# hackfest.net
KiCad netlist of a schematic drawn in EAGLE
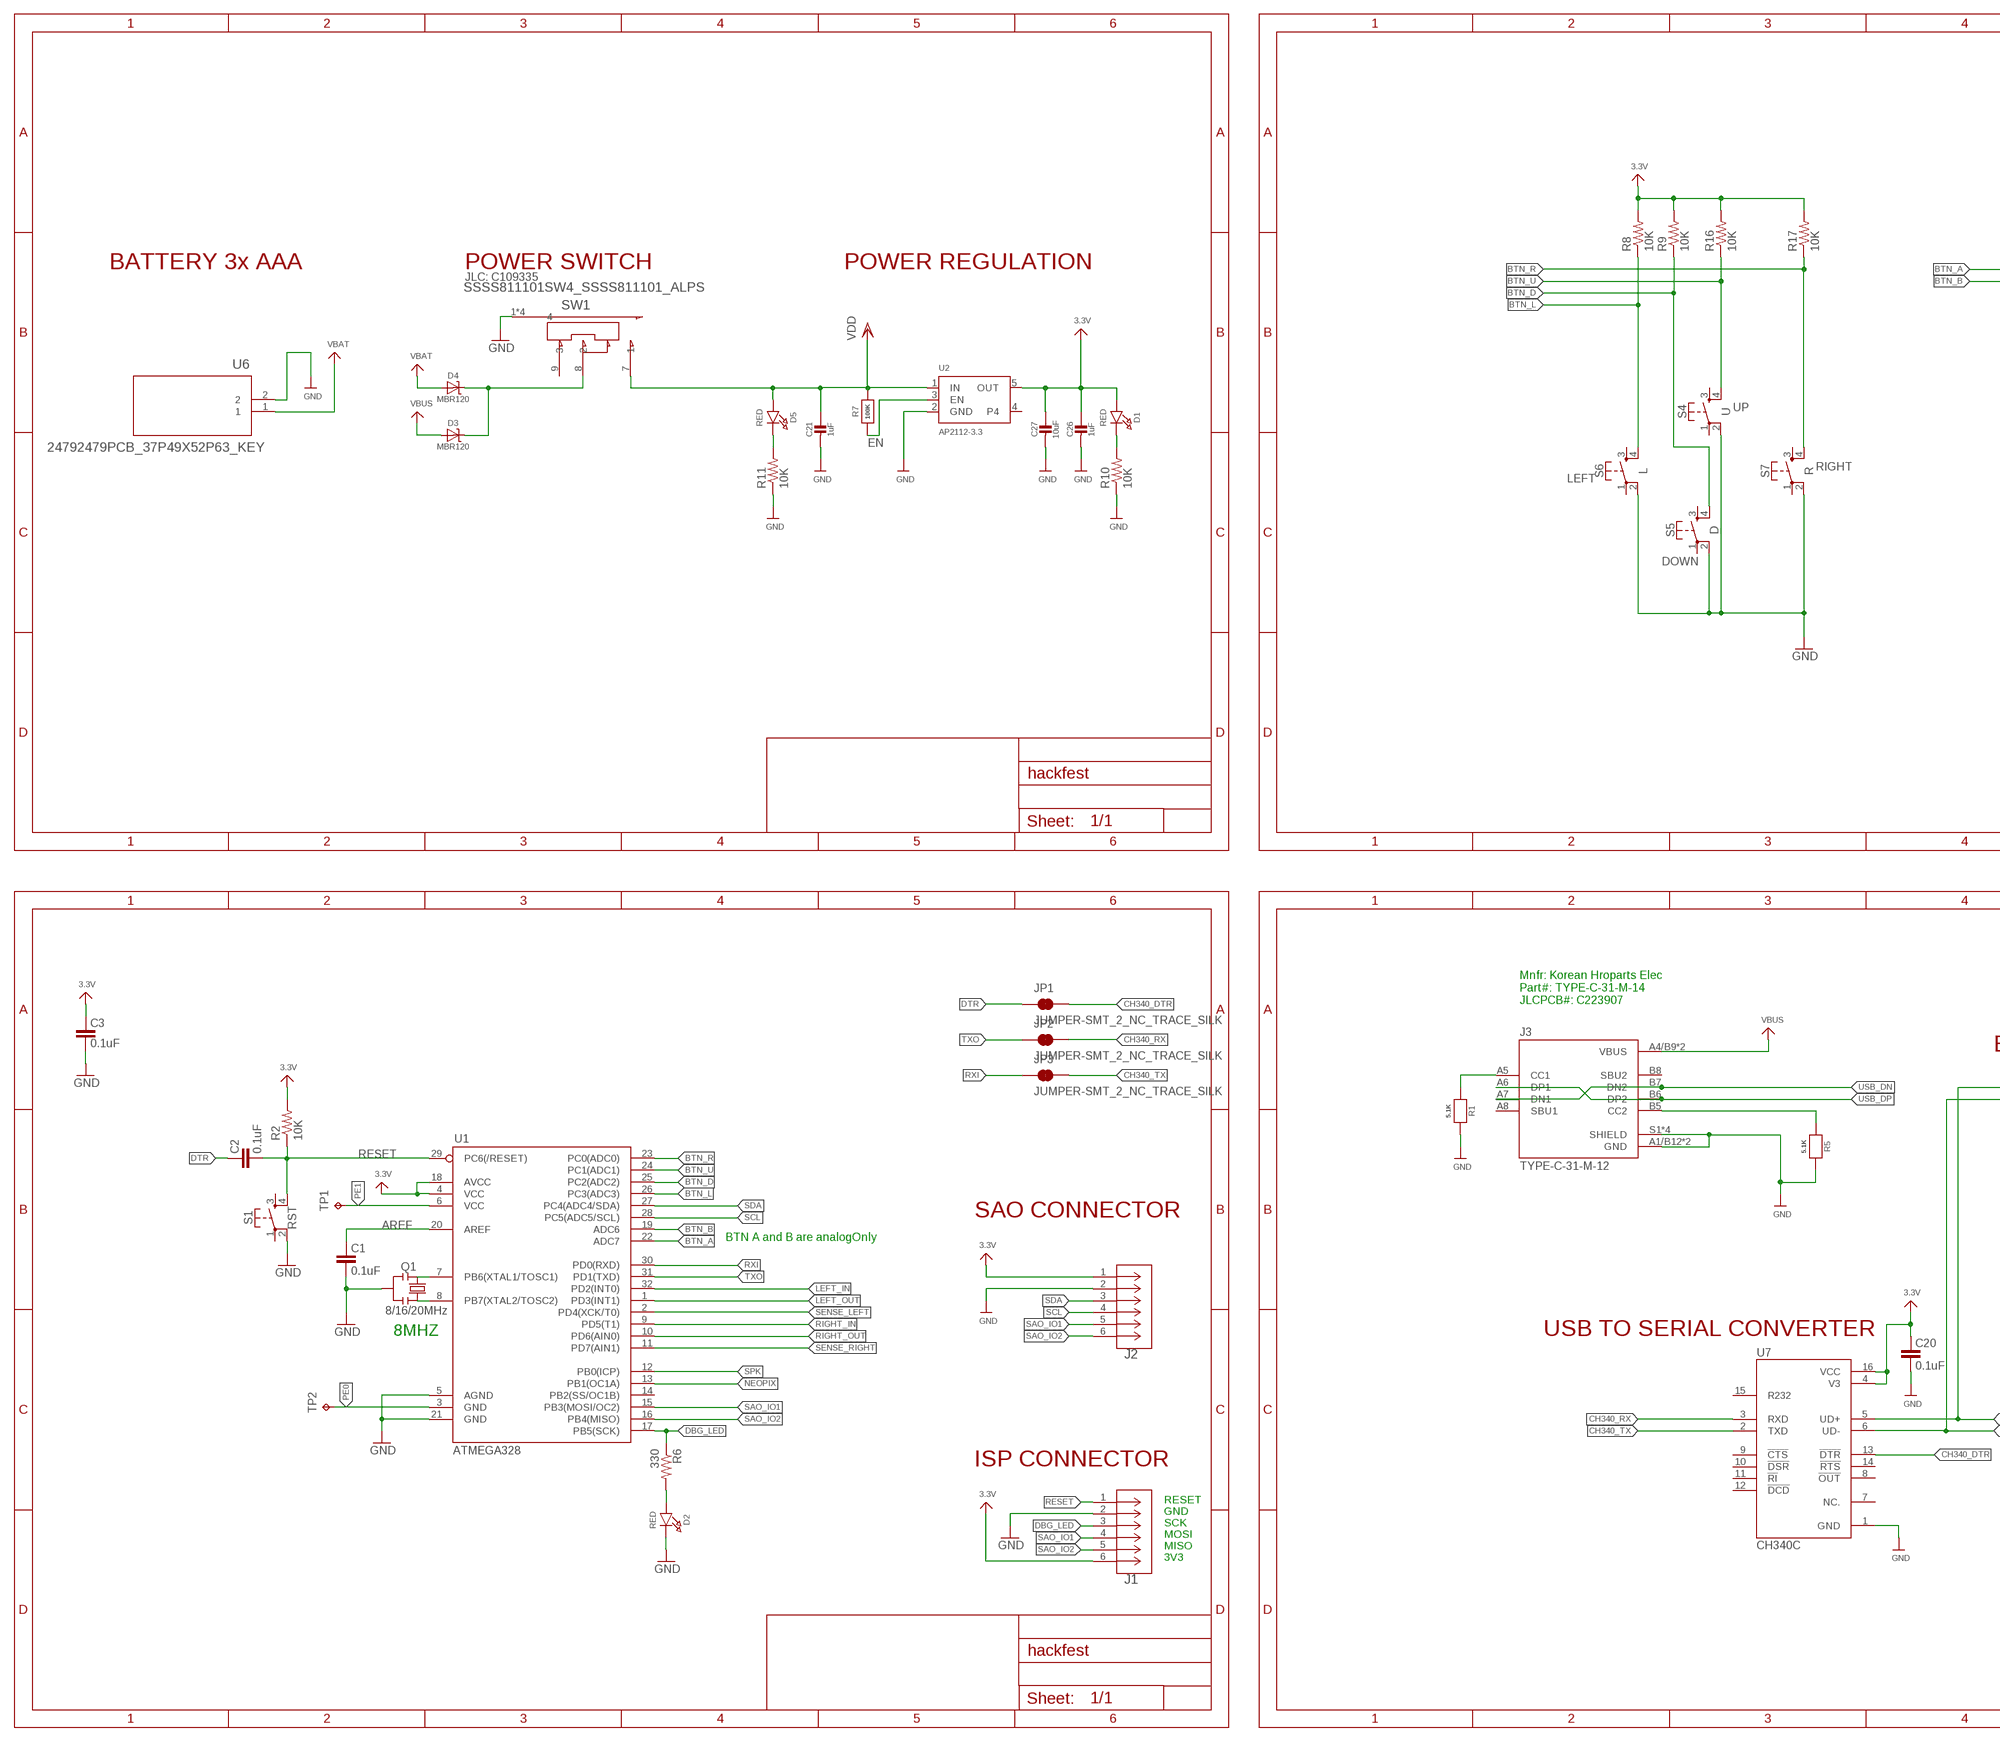
[diagram p0: schematic, sheet 1, part 1 of 2]
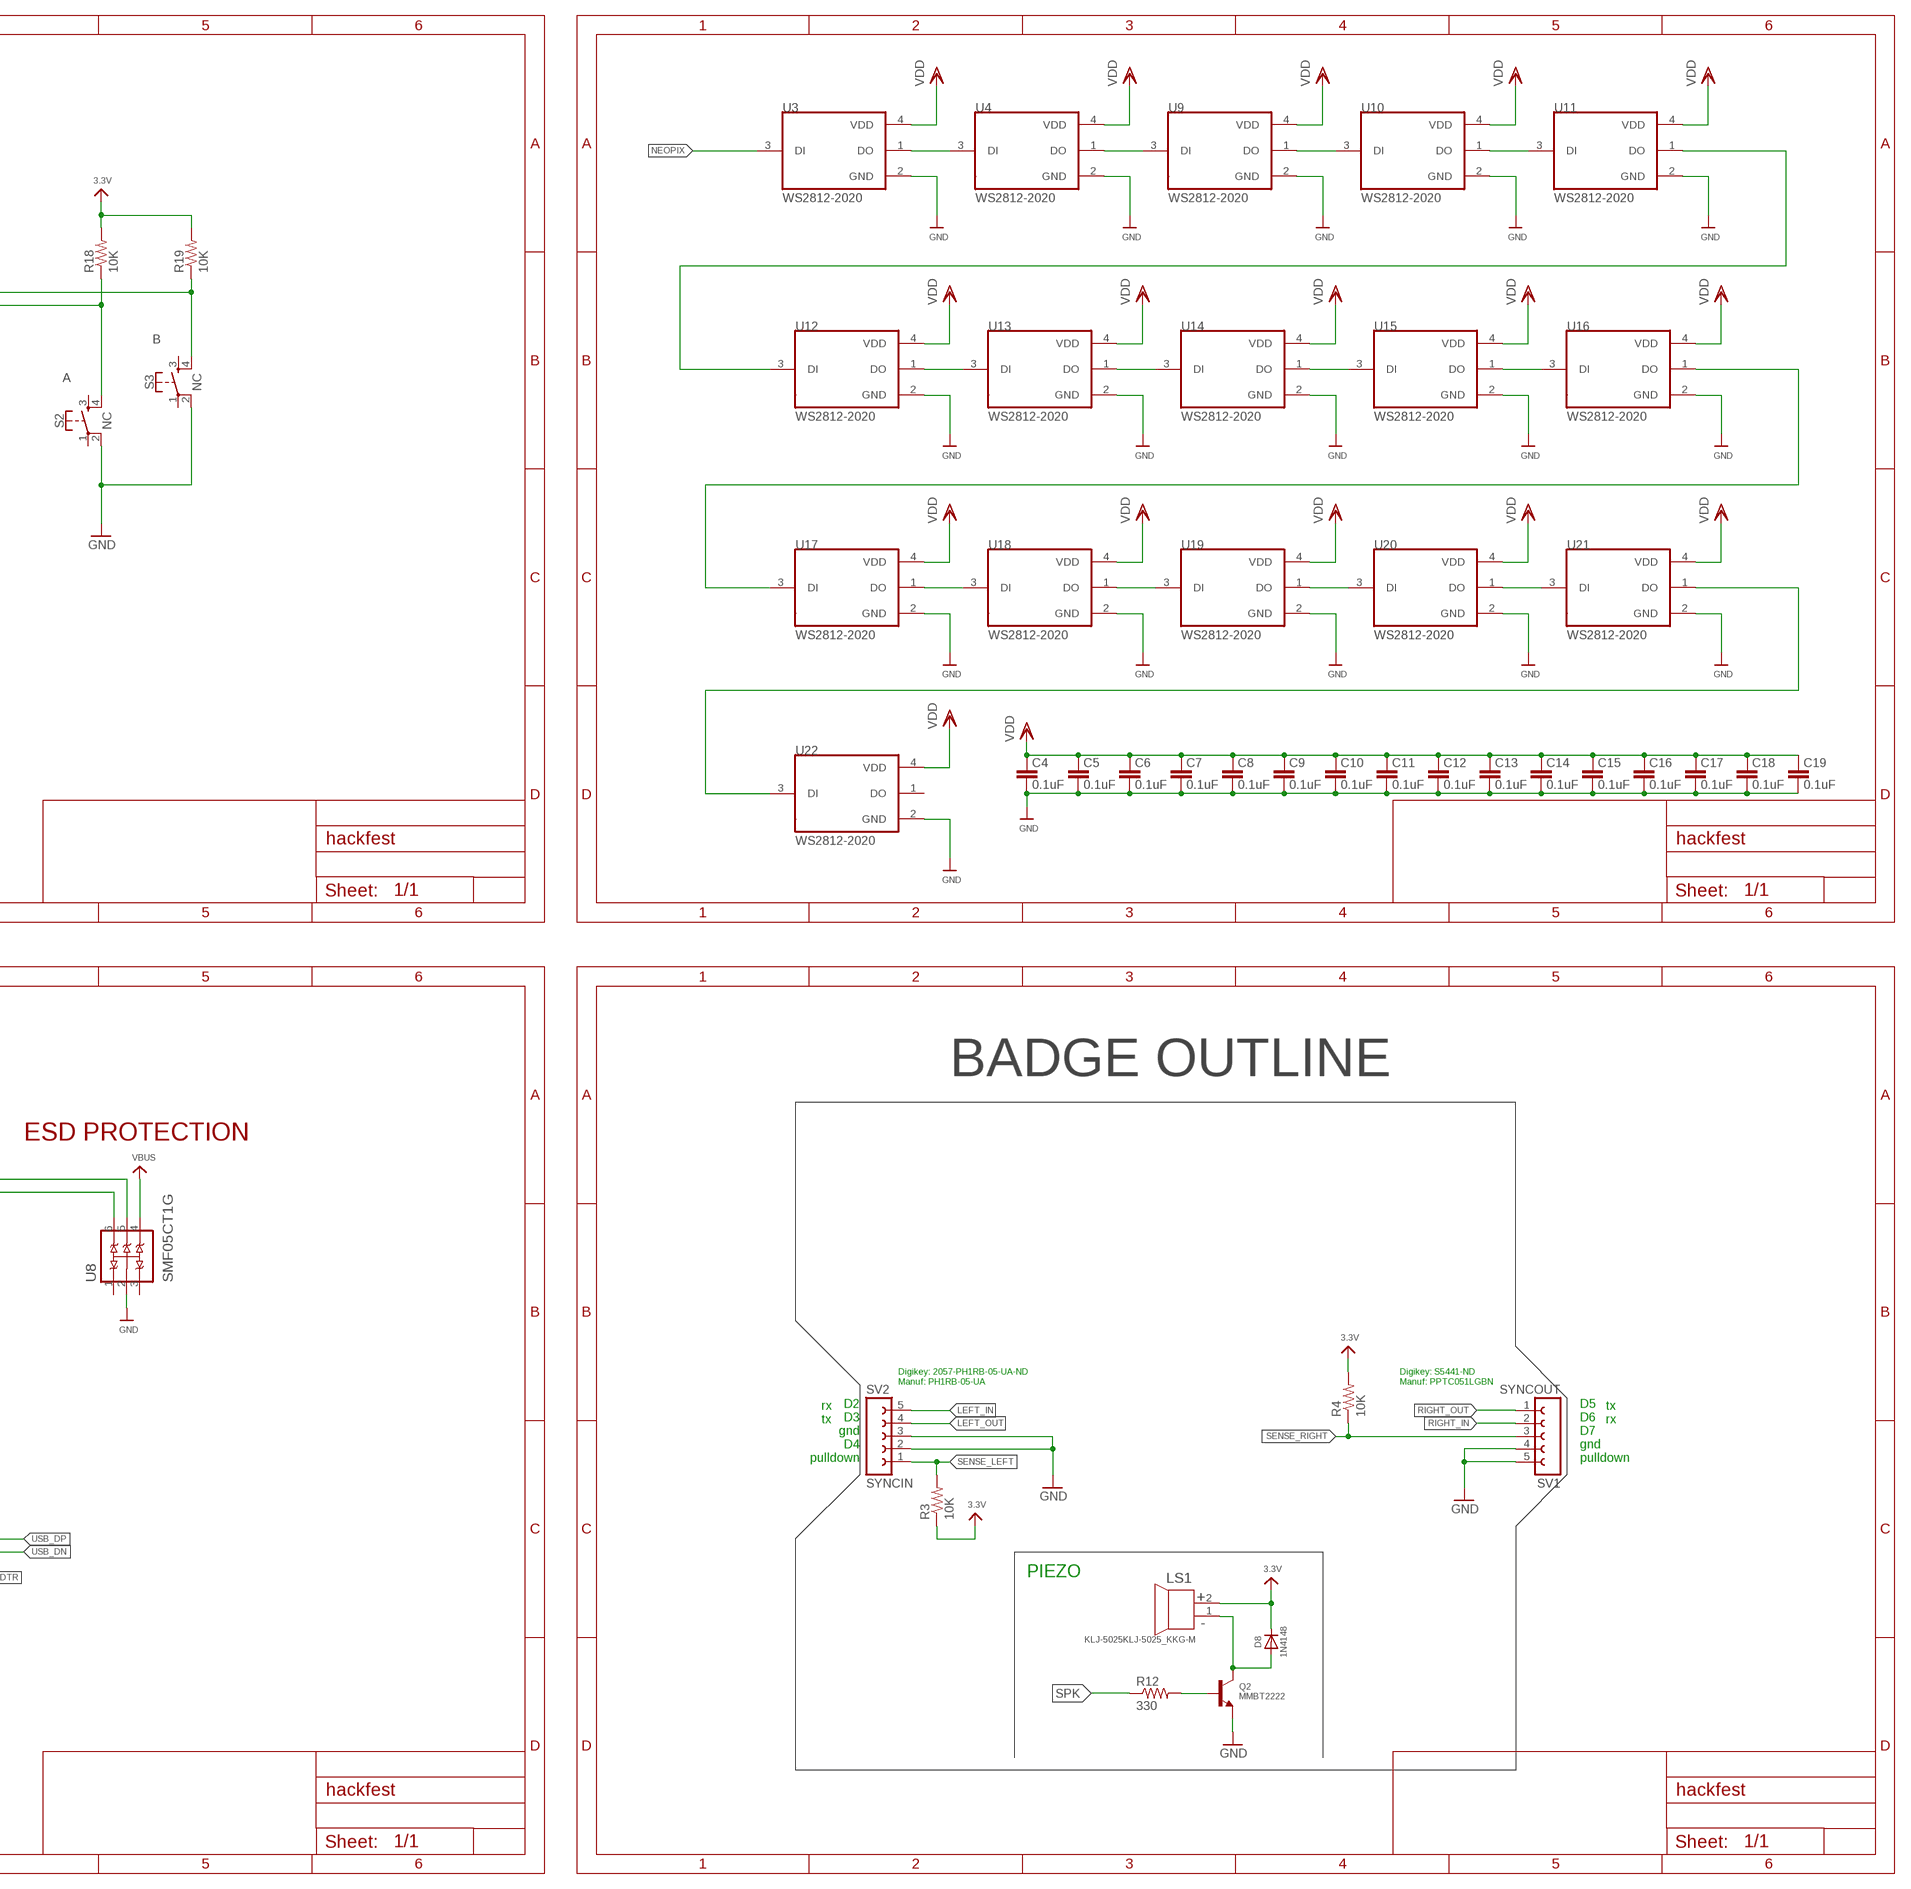
[diagram p1: schematic, sheet 1, part 2 of 2]

(export (version "E")
  (design (tool "Eeschema 10.0.6"))
  (components
    (comp (ref "C1")
      (value "0.1uF")
      (footprint "eagle-import:0603-CAP")
      (libsource (lib "eagle-import") (part "CAP0603-CAP"))
    )
    (comp (ref "C2")
      (value "0.1uF")
      (footprint "eagle-import:0603-CAP")
      (libsource (lib "eagle-import") (part "CAP0603-CAP"))
    )
    (comp (ref "C3")
      (value "0.1uF")
      (footprint "eagle-import:0603-CAP")
      (libsource (lib "eagle-import") (part "CAP0603-CAP"))
    )
    (comp (ref "C4")
      (value "0.1uF")
      (footprint "eagle-import:0603-CAP")
      (libsource (lib "eagle-import") (part "CAP0603-CAP"))
    )
    (comp (ref "C5")
      (value "0.1uF")
      (footprint "eagle-import:0603-CAP")
      (libsource (lib "eagle-import") (part "CAP0603-CAP"))
    )
    (comp (ref "C6")
      (value "0.1uF")
      (footprint "eagle-import:0603-CAP")
      (libsource (lib "eagle-import") (part "CAP0603-CAP"))
    )
    (comp (ref "C7")
      (value "0.1uF")
      (footprint "eagle-import:0603-CAP")
      (libsource (lib "eagle-import") (part "CAP0603-CAP"))
    )
    (comp (ref "C8")
      (value "0.1uF")
      (footprint "eagle-import:0603-CAP")
      (libsource (lib "eagle-import") (part "CAP0603-CAP"))
    )
    (comp (ref "C9")
      (value "0.1uF")
      (footprint "eagle-import:0603-CAP")
      (libsource (lib "eagle-import") (part "CAP0603-CAP"))
    )
    (comp (ref "C10")
      (value "0.1uF")
      (footprint "eagle-import:0603-CAP")
      (libsource (lib "eagle-import") (part "CAP0603-CAP"))
    )
    (comp (ref "C11")
      (value "0.1uF")
      (footprint "eagle-import:0603-CAP")
      (libsource (lib "eagle-import") (part "CAP0603-CAP"))
    )
    (comp (ref "C12")
      (value "0.1uF")
      (footprint "eagle-import:0603-CAP")
      (libsource (lib "eagle-import") (part "CAP0603-CAP"))
    )
    (comp (ref "C13")
      (value "0.1uF")
      (footprint "eagle-import:0603-CAP")
      (libsource (lib "eagle-import") (part "CAP0603-CAP"))
    )
    (comp (ref "C14")
      (value "0.1uF")
      (footprint "eagle-import:0603-CAP")
      (libsource (lib "eagle-import") (part "CAP0603-CAP"))
    )
    (comp (ref "C15")
      (value "0.1uF")
      (footprint "eagle-import:0603-CAP")
      (libsource (lib "eagle-import") (part "CAP0603-CAP"))
    )
    (comp (ref "C16")
      (value "0.1uF")
      (footprint "eagle-import:0603-CAP")
      (libsource (lib "eagle-import") (part "CAP0603-CAP"))
    )
    (comp (ref "C17")
      (value "0.1uF")
      (footprint "eagle-import:0603-CAP")
      (libsource (lib "eagle-import") (part "CAP0603-CAP"))
    )
    (comp (ref "C18")
      (value "0.1uF")
      (footprint "eagle-import:0603-CAP")
      (libsource (lib "eagle-import") (part "CAP0603-CAP"))
    )
    (comp (ref "C19")
      (value "0.1uF")
      (footprint "eagle-import:0603-CAP")
      (libsource (lib "eagle-import") (part "CAP0603-CAP"))
    )
    (comp (ref "C20")
      (value "0.1uF")
      (footprint "eagle-import:0603-CAP")
      (libsource (lib "eagle-import") (part "CAP0603-CAP"))
    )
    (comp (ref "C21")
      (value "1uF")
      (footprint "eagle-import:0603-NO@1")
      (libsource (lib "eagle-import") (part "CAP_CERAMIC0603_NO"))
    )
    (comp (ref "C26")
      (value "1uF")
      (footprint "eagle-import:0603-NO@1")
      (libsource (lib "eagle-import") (part "CAP_CERAMIC0603_NO"))
    )
    (comp (ref "C27")
      (value "10uF")
      (footprint "eagle-import:0805-NO")
      (libsource (lib "eagle-import") (part "CAP_CERAMIC0805-NOOUTLINE"))
    )
    (comp (ref "D1")
      (value "RED")
      (footprint "eagle-import:CHIPLED_0805_NOOUTLINE")
      (libsource (lib "eagle-import") (part "LED0805_NOOUTLINE"))
    )
    (comp (ref "D2")
      (value "RED")
      (footprint "eagle-import:CHIPLED_0805_NOOUTLINE")
      (libsource (lib "eagle-import") (part "LED0805_NOOUTLINE"))
    )
    (comp (ref "D3")
      (value "MBR120")
      (footprint "eagle-import:SOD-123")
      (libsource (lib "eagle-import") (part "DIODE-SCHOTTKYSOD-123"))
    )
    (comp (ref "D4")
      (value "MBR120")
      (footprint "eagle-import:SOD-123")
      (libsource (lib "eagle-import") (part "DIODE-SCHOTTKYSOD-123"))
    )
    (comp (ref "D5")
      (value "RED")
      (footprint "eagle-import:CHIPLED_0805_NOOUTLINE")
      (libsource (lib "eagle-import") (part "LED0805_NOOUTLINE"))
    )
    (comp (ref "D8")
      (value "1N4148")
      (footprint "eagle-import:SOD-323")
      (libsource (lib "eagle-import") (part "DIODESOD-323"))
    )
    (comp (ref "J1")
      (value "SSW-103-22-F-D-VS-K-TRCON3_SSW-D-DUMZ_HDR_SAI")
      (footprint "eagle-import:CON3_SSW-D-DUMZ_HDR_SAI")
      (fields
        (field (name "MANUFACTURER_PART_NUMBER") "SSW-103-22-F-D-VS-K-TR")
        (field (name "COPYRIGHT") "Copyright (C) 2022 Ultra Librarian. All rights reserved.")
      )
      (libsource (lib "eagle-import") (part "SSW-103-22-F-D-VS-K-TRCON3_SSW-D-DUMZ_HDR_SAI"))
    )
    (comp (ref "J2")
      (value "SSW-103-22-F-D-VS-K-TRCON3_SSW-D-DUMZ_HDR_SAI")
      (footprint "eagle-import:CON3_SSW-D-DUMZ_HDR_SAI")
      (fields
        (field (name "MANUFACTURER_PART_NUMBER") "SSW-103-22-F-D-VS-K-TR")
        (field (name "COPYRIGHT") "Copyright (C) 2022 Ultra Librarian. All rights reserved.")
      )
      (libsource (lib "eagle-import") (part "SSW-103-22-F-D-VS-K-TRCON3_SSW-D-DUMZ_HDR_SAI"))
    )
    (comp (ref "J3")
      (value "TYPE-C-31-M-12")
      (footprint "eagle-import:HRO_TYPE-C-31-M-12")
      (fields (field (name "MANUFACTURER") "HRO Electronics Co., Ltd."))
      (libsource (lib "eagle-import") (part "TYPE-C-31-M-12"))
    )
    (comp (ref "JP1")
      (value "JUMPER-SMT_2_NC_TRACE_SILK")
      (footprint "eagle-import:SMT-JUMPER_2_NC_TRACE_SILK")
      (libsource (lib "eagle-import") (part "JUMPER-SMT_2_NC_TRACE_SILK"))
    )
    (comp (ref "JP2")
      (value "JUMPER-SMT_2_NC_TRACE_SILK")
      (footprint "eagle-import:SMT-JUMPER_2_NC_TRACE_SILK")
      (libsource (lib "eagle-import") (part "JUMPER-SMT_2_NC_TRACE_SILK"))
    )
    (comp (ref "JP3")
      (value "JUMPER-SMT_2_NC_TRACE_SILK")
      (footprint "eagle-import:SMT-JUMPER_2_NC_TRACE_SILK")
      (libsource (lib "eagle-import") (part "JUMPER-SMT_2_NC_TRACE_SILK"))
    )
    (comp (ref "LS1")
      (value "KLJ-5025KLJ-5025_KKG-M")
      (footprint "eagle-import:KLJ-5025_KKG-M")
      (fields
        (field (name "MANUFACTURER_PART_NUMBER") "KLJ-5025")
        (field (name "COPYRIGHT") "Copyright (C) 2024 Ultra Librarian. All rights reserved.")
      )
      (libsource (lib "eagle-import") (part "KLJ-5025KLJ-5025_KKG-M"))
    )
    (comp (ref "Q1")
      (value "8/16/20MHz")
      (footprint "eagle-import:RESONATOR-SMD-1_1")
      (libsource (lib "eagle-import") (part "RESONATOR1{colon}1"))
    )
    (comp (ref "Q2")
      (value "MMBT2222")
      (footprint "eagle-import:SOT23-WIDE")
      (libsource (lib "eagle-import") (part "TRANSISTOR_NPNWIDE"))
    )
    (comp (ref "R1")
      (value "5.1K")
      (footprint "eagle-import:0603-NO")
      (libsource (lib "eagle-import") (part "RESISTOR_0603_NOOUT"))
    )
    (comp (ref "R2")
      (value "10K")
      (footprint "eagle-import:0603-RES")
      (libsource (lib "eagle-import") (part "RESISTOR0603-RES"))
    )
    (comp (ref "R3")
      (value "10K")
      (footprint "eagle-import:0603-RES")
      (libsource (lib "eagle-import") (part "RESISTOR0603-RES"))
    )
    (comp (ref "R4")
      (value "10K")
      (footprint "eagle-import:0603-RES")
      (libsource (lib "eagle-import") (part "RESISTOR0603-RES"))
    )
    (comp (ref "R5")
      (value "5.1K")
      (footprint "eagle-import:0603-NO")
      (libsource (lib "eagle-import") (part "RESISTOR_0603_NOOUT"))
    )
    (comp (ref "R6")
      (value "330")
      (footprint "eagle-import:0603-RES")
      (libsource (lib "eagle-import") (part "RESISTOR0603-RES"))
    )
    (comp (ref "R7")
      (value "100K")
      (footprint "eagle-import:0603-NO")
      (libsource (lib "eagle-import") (part "RESISTOR_0603_NOOUT"))
    )
    (comp (ref "R8")
      (value "10K")
      (footprint "eagle-import:0603-RES")
      (libsource (lib "eagle-import") (part "RESISTOR0603-RES"))
    )
    (comp (ref "R9")
      (value "10K")
      (footprint "eagle-import:0603-RES")
      (libsource (lib "eagle-import") (part "RESISTOR0603-RES"))
    )
    (comp (ref "R10")
      (value "10K")
      (footprint "eagle-import:0603-RES")
      (libsource (lib "eagle-import") (part "RESISTOR0603-RES"))
    )
    (comp (ref "R11")
      (value "10K")
      (footprint "eagle-import:0603-RES")
      (libsource (lib "eagle-import") (part "RESISTOR0603-RES"))
    )
    (comp (ref "R12")
      (value "330")
      (footprint "eagle-import:0603-RES")
      (libsource (lib "eagle-import") (part "RESISTOR0603-RES"))
    )
    (comp (ref "R16")
      (value "10K")
      (footprint "eagle-import:0603-RES")
      (libsource (lib "eagle-import") (part "RESISTOR0603-RES"))
    )
    (comp (ref "R17")
      (value "10K")
      (footprint "eagle-import:0603-RES")
      (libsource (lib "eagle-import") (part "RESISTOR0603-RES"))
    )
    (comp (ref "R18")
      (value "10K")
      (footprint "eagle-import:0603-RES")
      (libsource (lib "eagle-import") (part "RESISTOR0603-RES"))
    )
    (comp (ref "R19")
      (value "10K")
      (footprint "eagle-import:0603-RES")
      (libsource (lib "eagle-import") (part "RESISTOR0603-RES"))
    )
    (comp (ref "S1")
      (value "RST")
      (footprint "eagle-import:TACTILE_SWITCH_SMD_5.2MM")
      (libsource (lib "eagle-import") (part "MOMENTARY-SWITCH-SPST-2-SMD-5.2MM"))
    )
    (comp (ref "S2")
      (value "NC")
      (footprint "eagle-import:TACTILE_SWITCH_SMD_5.2MM")
      (libsource (lib "eagle-import") (part "MOMENTARY-SWITCH-SPST-2-SMD-5.2MM"))
    )
    (comp (ref "S3")
      (value "NC")
      (footprint "eagle-import:TACTILE_SWITCH_SMD_5.2MM")
      (libsource (lib "eagle-import") (part "MOMENTARY-SWITCH-SPST-2-SMD-5.2MM"))
    )
    (comp (ref "S4")
      (value "U")
      (footprint "eagle-import:TACTILE_SWITCH_SMD_5.2MM")
      (libsource (lib "eagle-import") (part "MOMENTARY-SWITCH-SPST-2-SMD-5.2MM"))
    )
    (comp (ref "S5")
      (value "D")
      (footprint "eagle-import:TACTILE_SWITCH_SMD_5.2MM")
      (libsource (lib "eagle-import") (part "MOMENTARY-SWITCH-SPST-2-SMD-5.2MM"))
    )
    (comp (ref "S6")
      (value "L")
      (footprint "eagle-import:TACTILE_SWITCH_SMD_5.2MM")
      (libsource (lib "eagle-import") (part "MOMENTARY-SWITCH-SPST-2-SMD-5.2MM"))
    )
    (comp (ref "S7")
      (value "R")
      (footprint "eagle-import:TACTILE_SWITCH_SMD_5.2MM")
      (libsource (lib "eagle-import") (part "MOMENTARY-SWITCH-SPST-2-SMD-5.2MM"))
    )
    (comp (ref "SV1")
      (value "SYNCOUT")
      (footprint "eagle-import:FE05W")
      (libsource (lib "eagle-import") (part "FE05W"))
    )
    (comp (ref "SV2")
      (value "SYNCIN")
      (footprint "eagle-import:FE05W")
      (libsource (lib "eagle-import") (part "FE05W"))
    )
    (comp (ref "SW1")
      (value "SSSS811101SW4_SSSS811101_ALPS")
      (footprint "eagle-import:SW4_SSSS811101_ALPS")
      (fields
        (field (name "MANUFACTURER_PART_NUMBER") "SSSS811101")
        (field (name "COPYRIGHT") "Copyright (C) 2023 Ultra Librarian. All rights reserved.")
      )
      (libsource (lib "eagle-import") (part "SSSS811101SW4_SSSS811101_ALPS"))
    )
    (comp (ref "TP1")
      (value "TPB1,27")
      (footprint "eagle-import:B1,27")
      (libsource (lib "eagle-import") (part "TPB1,27"))
    )
    (comp (ref "TP2")
      (value "TPB1,27")
      (footprint "eagle-import:B1,27")
      (libsource (lib "eagle-import") (part "TPB1,27"))
    )
    (comp (ref "U1")
      (value "ATMEGA328")
      (footprint "eagle-import:TQFP32-08")
      (libsource (lib "eagle-import") (part "ATMEGA168"))
    )
    (comp (ref "U2")
      (value "AP2112-3.3")
      (footprint "eagle-import:SOT23-5")
      (libsource (lib "eagle-import") (part "VREG_SOT23-5"))
    )
    (comp (ref "U3")
      (value "WS2812-2020")
      (footprint "eagle-import:LED_WS2812-2020")
      (fields (field (name "MF") "Worldsemi"))
      (libsource (lib "eagle-import") (part "WS2812-2020"))
    )
    (comp (ref "U4")
      (value "WS2812-2020")
      (footprint "eagle-import:LED_WS2812-2020")
      (fields (field (name "MF") "Worldsemi"))
      (libsource (lib "eagle-import") (part "WS2812-2020"))
    )
    (comp (ref "U6")
      (value "24792479PCB_37P49X52P63_KEY")
      (footprint "eagle-import:2479PCB_37P49X52P63_KEY")
      (fields
        (field (name "MANUFACTURER_PART_NUMBER") "2479")
        (field (name "COPYRIGHT") "Copyright (C) 2022 Ultra Librarian. All rights reserved.")
      )
      (libsource (lib "eagle-import") (part "24792479PCB_37P49X52P63_KEY"))
    )
    (comp (ref "U7")
      (value "CH340C")
      (footprint "eagle-import:SOIC127P600X180-16N")
      (fields (field (name "MF") "WCH"))
      (libsource (lib "eagle-import") (part "CH340C"))
    )
    (comp (ref "U8")
      (value "SMF05CT1G")
      (footprint "eagle-import:SOT65P210X110-6N")
      (fields (field (name "MF") "ON Semiconductor"))
      (libsource (lib "eagle-import") (part "SMF05CT1G"))
    )
    (comp (ref "U9")
      (value "WS2812-2020")
      (footprint "eagle-import:LED_WS2812-2020")
      (fields (field (name "MF") "Worldsemi"))
      (libsource (lib "eagle-import") (part "WS2812-2020"))
    )
    (comp (ref "U10")
      (value "WS2812-2020")
      (footprint "eagle-import:LED_WS2812-2020")
      (fields (field (name "MF") "Worldsemi"))
      (libsource (lib "eagle-import") (part "WS2812-2020"))
    )
    (comp (ref "U11")
      (value "WS2812-2020")
      (footprint "eagle-import:LED_WS2812-2020")
      (fields (field (name "MF") "Worldsemi"))
      (libsource (lib "eagle-import") (part "WS2812-2020"))
    )
    (comp (ref "U12")
      (value "WS2812-2020")
      (footprint "eagle-import:LED_WS2812-2020")
      (fields (field (name "MF") "Worldsemi"))
      (libsource (lib "eagle-import") (part "WS2812-2020"))
    )
    (comp (ref "U13")
      (value "WS2812-2020")
      (footprint "eagle-import:LED_WS2812-2020")
      (fields (field (name "MF") "Worldsemi"))
      (libsource (lib "eagle-import") (part "WS2812-2020"))
    )
    (comp (ref "U14")
      (value "WS2812-2020")
      (footprint "eagle-import:LED_WS2812-2020")
      (fields (field (name "MF") "Worldsemi"))
      (libsource (lib "eagle-import") (part "WS2812-2020"))
    )
    (comp (ref "U15")
      (value "WS2812-2020")
      (footprint "eagle-import:LED_WS2812-2020")
      (fields (field (name "MF") "Worldsemi"))
      (libsource (lib "eagle-import") (part "WS2812-2020"))
    )
    (comp (ref "U16")
      (value "WS2812-2020")
      (footprint "eagle-import:LED_WS2812-2020")
      (fields (field (name "MF") "Worldsemi"))
      (libsource (lib "eagle-import") (part "WS2812-2020"))
    )
    (comp (ref "U17")
      (value "WS2812-2020")
      (footprint "eagle-import:LED_WS2812-2020")
      (fields (field (name "MF") "Worldsemi"))
      (libsource (lib "eagle-import") (part "WS2812-2020"))
    )
    (comp (ref "U18")
      (value "WS2812-2020")
      (footprint "eagle-import:LED_WS2812-2020")
      (fields (field (name "MF") "Worldsemi"))
      (libsource (lib "eagle-import") (part "WS2812-2020"))
    )
    (comp (ref "U19")
      (value "WS2812-2020")
      (footprint "eagle-import:LED_WS2812-2020")
      (fields (field (name "MF") "Worldsemi"))
      (libsource (lib "eagle-import") (part "WS2812-2020"))
    )
    (comp (ref "U20")
      (value "WS2812-2020")
      (footprint "eagle-import:LED_WS2812-2020")
      (fields (field (name "MF") "Worldsemi"))
      (libsource (lib "eagle-import") (part "WS2812-2020"))
    )
    (comp (ref "U21")
      (value "WS2812-2020")
      (footprint "eagle-import:LED_WS2812-2020")
      (fields (field (name "MF") "Worldsemi"))
      (libsource (lib "eagle-import") (part "WS2812-2020"))
    )
    (comp (ref "U22")
      (value "WS2812-2020")
      (footprint "eagle-import:LED_WS2812-2020")
      (fields (field (name "MF") "Worldsemi"))
      (libsource (lib "eagle-import") (part "WS2812-2020"))
    )
  )
  (nets
    (net (code "1") (name "/AREF") (class "Default")
      (node (ref "C1") (pin "2") (pinfunction "2_2") (pintype "passive"))
      (node (ref "U1") (pin "20") (pinfunction "AREF_20") (pintype "bidirectional"))
    )
    (net (code "2") (name "/EN") (class "Default")
      (node (ref "R7") (pin "1") (pinfunction "1_1") (pintype "passive"))
      (node (ref "U2") (pin "3") (pinfunction "EN_3") (pintype "input"))
    )
    (net (code "3") (name "3.3V") (class "Default")
      (node (ref "C20") (pin "2") (pinfunction "2_2") (pintype "passive"))
      (node (ref "C26") (pin "1") (pinfunction "1_1") (pintype "passive"))
      (node (ref "C27") (pin "1") (pinfunction "1_1") (pintype "passive"))
      (node (ref "C3") (pin "2") (pinfunction "2_2") (pintype "passive"))
      (node (ref "D1") (pin "A") (pinfunction "A_A") (pintype "passive"))
      (node (ref "D8") (pin "C") (pinfunction "C_C") (pintype "passive"))
      (node (ref "J1") (pin "6") (pinfunction "6_6") (pintype "passive"))
      (node (ref "J2") (pin "1") (pinfunction "1_1") (pintype "passive"))
      (node (ref "LS1") (pin "2") (pinfunction "2_2") (pintype "passive"))
      (node (ref "R16") (pin "2") (pinfunction "2_2") (pintype "passive"))
      (node (ref "R17") (pin "2") (pinfunction "2_2") (pintype "passive"))
      (node (ref "R18") (pin "2") (pinfunction "2_2") (pintype "passive"))
      (node (ref "R19") (pin "2") (pinfunction "2_2") (pintype "passive"))
      (node (ref "R2") (pin "2") (pinfunction "2_2") (pintype "passive"))
      (node (ref "R3") (pin "1") (pinfunction "1_1") (pintype "passive"))
      (node (ref "R4") (pin "2") (pinfunction "2_2") (pintype "passive"))
      (node (ref "R8") (pin "2") (pinfunction "2_2") (pintype "passive"))
      (node (ref "R9") (pin "2") (pinfunction "2_2") (pintype "passive"))
      (node (ref "U1") (pin "18") (pinfunction "AVCC_18") (pintype "bidirectional"))
      (node (ref "U1") (pin "4") (pinfunction "VCC_4") (pintype "bidirectional"))
      (node (ref "U2") (pin "5") (pinfunction "OUT_5") (pintype "power_in"))
      (node (ref "U7") (pin "16") (pinfunction "VCC_16") (pintype "power_in"))
      (node (ref "U7") (pin "4") (pinfunction "V3_4") (pintype "power_in"))
    )
    (net (code "4") (name "BTN_A") (class "Default")
      (node (ref "R19") (pin "1") (pinfunction "1_1") (pintype "passive"))
      (node (ref "S3") (pin "4") (pinfunction "4_4") (pintype "passive"))
      (node (ref "U1") (pin "22") (pinfunction "ADC7_22") (pintype "bidirectional"))
    )
    (net (code "5") (name "BTN_B") (class "Default")
      (node (ref "R18") (pin "1") (pinfunction "1_1") (pintype "passive"))
      (node (ref "S2") (pin "4") (pinfunction "4_4") (pintype "passive"))
      (node (ref "U1") (pin "19") (pinfunction "ADC6_19") (pintype "bidirectional"))
    )
    (net (code "6") (name "BTN_D") (class "Default")
      (node (ref "R9") (pin "1") (pinfunction "1_1") (pintype "passive"))
      (node (ref "S5") (pin "4") (pinfunction "4_4") (pintype "passive"))
      (node (ref "U1") (pin "25") (pinfunction "PC2(ADC2)_25") (pintype "bidirectional"))
    )
    (net (code "7") (name "BTN_L") (class "Default")
      (node (ref "R8") (pin "1") (pinfunction "1_1") (pintype "passive"))
      (node (ref "S6") (pin "4") (pinfunction "4_4") (pintype "passive"))
      (node (ref "U1") (pin "26") (pinfunction "PC3(ADC3)_26") (pintype "bidirectional"))
    )
    (net (code "8") (name "BTN_R") (class "Default")
      (node (ref "R17") (pin "1") (pinfunction "1_1") (pintype "passive"))
      (node (ref "S7") (pin "4") (pinfunction "4_4") (pintype "passive"))
      (node (ref "U1") (pin "23") (pinfunction "PC0(ADC0)_23") (pintype "bidirectional"))
    )
    (net (code "9") (name "BTN_U") (class "Default")
      (node (ref "R16") (pin "1") (pinfunction "1_1") (pintype "passive"))
      (node (ref "S4") (pin "4") (pinfunction "4_4") (pintype "passive"))
      (node (ref "U1") (pin "24") (pinfunction "PC1(ADC1)_24") (pintype "bidirectional"))
    )
    (net (code "10") (name "CH340_DTR") (class "Default")
      (node (ref "JP1") (pin "2") (pinfunction "2_2") (pintype "passive"))
      (node (ref "U7") (pin "13") (pinfunction "~{DTR}_13") (pintype "output"))
    )
    (net (code "11") (name "CH340_RX") (class "Default")
      (node (ref "JP2") (pin "2") (pinfunction "2_2") (pintype "passive"))
      (node (ref "U7") (pin "3") (pinfunction "RXD_3") (pintype "input"))
    )
    (net (code "12") (name "CH340_TX") (class "Default")
      (node (ref "JP3") (pin "2") (pinfunction "2_2") (pintype "passive"))
      (node (ref "U7") (pin "2") (pinfunction "TXD_2") (pintype "output"))
    )
    (net (code "13") (name "DBG_LED") (class "Default")
      (node (ref "J1") (pin "3") (pinfunction "3_3") (pintype "passive"))
      (node (ref "R6") (pin "1") (pinfunction "1_1") (pintype "passive"))
      (node (ref "U1") (pin "17") (pinfunction "PB5(SCK)_17") (pintype "bidirectional"))
    )
    (net (code "14") (name "DTR") (class "Default")
      (node (ref "C2") (pin "2") (pinfunction "2_2") (pintype "passive"))
      (node (ref "JP1") (pin "1") (pinfunction "1_1") (pintype "passive"))
    )
    (net (code "15") (name "GND") (class "Default")
      (node (ref "C1") (pin "1") (pinfunction "1_1") (pintype "passive"))
      (node (ref "C10") (pin "1") (pinfunction "1_1") (pintype "passive"))
      (node (ref "C11") (pin "1") (pinfunction "1_1") (pintype "passive"))
      (node (ref "C12") (pin "1") (pinfunction "1_1") (pintype "passive"))
      (node (ref "C13") (pin "1") (pinfunction "1_1") (pintype "passive"))
      (node (ref "C14") (pin "1") (pinfunction "1_1") (pintype "passive"))
      (node (ref "C15") (pin "1") (pinfunction "1_1") (pintype "passive"))
      (node (ref "C16") (pin "1") (pinfunction "1_1") (pintype "passive"))
      (node (ref "C17") (pin "1") (pinfunction "1_1") (pintype "passive"))
      (node (ref "C18") (pin "1") (pinfunction "1_1") (pintype "passive"))
      (node (ref "C19") (pin "1") (pinfunction "1_1") (pintype "passive"))
      (node (ref "C20") (pin "1") (pinfunction "1_1") (pintype "passive"))
      (node (ref "C21") (pin "2") (pinfunction "2_2") (pintype "passive"))
      (node (ref "C26") (pin "2") (pinfunction "2_2") (pintype "passive"))
      (node (ref "C27") (pin "2") (pinfunction "2_2") (pintype "passive"))
      (node (ref "C3") (pin "1") (pinfunction "1_1") (pintype "passive"))
      (node (ref "C4") (pin "1") (pinfunction "1_1") (pintype "passive"))
      (node (ref "C5") (pin "1") (pinfunction "1_1") (pintype "passive"))
      (node (ref "C6") (pin "1") (pinfunction "1_1") (pintype "passive"))
      (node (ref "C7") (pin "1") (pinfunction "1_1") (pintype "passive"))
      (node (ref "C8") (pin "1") (pinfunction "1_1") (pintype "passive"))
      (node (ref "C9") (pin "1") (pinfunction "1_1") (pintype "passive"))
      (node (ref "D2") (pin "C") (pinfunction "C_C") (pintype "passive"))
      (node (ref "J1") (pin "2") (pinfunction "2_2") (pintype "passive"))
      (node (ref "J2") (pin "2") (pinfunction "2_2") (pintype "passive"))
      (node (ref "J3") (pin "A1/B12") (pinfunction "GND_A1/B12") (pintype "power_in"))
      (node (ref "J3") (pin "B1/A12") (pinfunction "GND_B1/A12") (pintype "power_in"))
      (node (ref "J3") (pin "S1") (pinfunction "SHIELD_S1") (pintype "passive"))
      (node (ref "J3") (pin "S2") (pinfunction "SHIELD_S2") (pintype "passive"))
      (node (ref "J3") (pin "S3") (pinfunction "SHIELD_S3") (pintype "passive"))
      (node (ref "J3") (pin "S4") (pinfunction "SHIELD_S4") (pintype "passive"))
      (node (ref "Q1") (pin "2") (pinfunction "2_2") (pintype "passive"))
      (node (ref "Q2") (pin "2") (pinfunction "E_2") (pintype "passive"))
      (node (ref "R1") (pin "2") (pinfunction "2_2") (pintype "passive"))
      (node (ref "R10") (pin "1") (pinfunction "1_1") (pintype "passive"))
      (node (ref "R11") (pin "1") (pinfunction "1_1") (pintype "passive"))
      (node (ref "R5") (pin "2") (pinfunction "2_2") (pintype "passive"))
      (node (ref "S1") (pin "2") (pinfunction "2_2") (pintype "passive"))
      (node (ref "S2") (pin "2") (pinfunction "2_2") (pintype "passive"))
      (node (ref "S3") (pin "2") (pinfunction "2_2") (pintype "passive"))
      (node (ref "S4") (pin "2") (pinfunction "2_2") (pintype "passive"))
      (node (ref "S5") (pin "2") (pinfunction "2_2") (pintype "passive"))
      (node (ref "S6") (pin "2") (pinfunction "2_2") (pintype "passive"))
      (node (ref "S7") (pin "2") (pinfunction "2_2") (pintype "passive"))
      (node (ref "SV1") (pin "4") (pinfunction "4_4") (pintype "passive"))
      (node (ref "SV1") (pin "5") (pinfunction "5_5") (pintype "passive"))
      (node (ref "SV2") (pin "2") (pinfunction "2_2") (pintype "passive"))
      (node (ref "SV2") (pin "3") (pinfunction "3_3") (pintype "passive"))
      (node (ref "SW1") (pin "1") (pinfunction "4_1") (pintype "passive"))
      (node (ref "SW1") (pin "2") (pinfunction "4_2") (pintype "passive"))
      (node (ref "SW1") (pin "3") (pinfunction "4_3") (pintype "passive"))
      (node (ref "SW1") (pin "4") (pinfunction "4_4") (pintype "passive"))
      (node (ref "U1") (pin "21") (pinfunction "GND_21") (pintype "bidirectional"))
      (node (ref "U1") (pin "5") (pinfunction "AGND_5") (pintype "bidirectional"))
      (node (ref "U10") (pin "2") (pinfunction "GND_2") (pintype "power_in"))
      (node (ref "U11") (pin "2") (pinfunction "GND_2") (pintype "power_in"))
      (node (ref "U12") (pin "2") (pinfunction "GND_2") (pintype "power_in"))
      (node (ref "U13") (pin "2") (pinfunction "GND_2") (pintype "power_in"))
      (node (ref "U14") (pin "2") (pinfunction "GND_2") (pintype "power_in"))
      (node (ref "U15") (pin "2") (pinfunction "GND_2") (pintype "power_in"))
      (node (ref "U16") (pin "2") (pinfunction "GND_2") (pintype "power_in"))
      (node (ref "U17") (pin "2") (pinfunction "GND_2") (pintype "power_in"))
      (node (ref "U18") (pin "2") (pinfunction "GND_2") (pintype "power_in"))
      (node (ref "U19") (pin "2") (pinfunction "GND_2") (pintype "power_in"))
      (node (ref "U2") (pin "2") (pinfunction "GND_2") (pintype "power_in"))
      (node (ref "U20") (pin "2") (pinfunction "GND_2") (pintype "power_in"))
      (node (ref "U21") (pin "2") (pinfunction "GND_2") (pintype "power_in"))
      (node (ref "U22") (pin "2") (pinfunction "GND_2") (pintype "power_in"))
      (node (ref "U3") (pin "2") (pinfunction "GND_2") (pintype "power_in"))
      (node (ref "U4") (pin "2") (pinfunction "GND_2") (pintype "power_in"))
      (node (ref "U6") (pin "2") (pinfunction "2_2") (pintype "passive"))
      (node (ref "U7") (pin "1") (pinfunction "GND_1") (pintype "power_in"))
      (node (ref "U8") (pin "2") (pinfunction "A_2") (pintype "passive"))
      (node (ref "U9") (pin "2") (pinfunction "GND_2") (pintype "power_in"))
    )
    (net (code "16") (name "LEFT_IN") (class "Default")
      (node (ref "SV2") (pin "5") (pinfunction "5_5") (pintype "passive"))
      (node (ref "U1") (pin "32") (pinfunction "PD2(INT0)_32") (pintype "bidirectional"))
    )
    (net (code "17") (name "LEFT_OUT") (class "Default")
      (node (ref "SV2") (pin "4") (pinfunction "4_4") (pintype "passive"))
      (node (ref "U1") (pin "1") (pinfunction "PD3(INT1)_1") (pintype "bidirectional"))
    )
    (net (code "18") (name "NEOPIX") (class "Default")
      (node (ref "U1") (pin "13") (pinfunction "PB1(OC1A)_13") (pintype "bidirectional"))
      (node (ref "U3") (pin "3") (pinfunction "DI_3") (pintype "input"))
    )
    (net (code "19") (name "Net-(D1-PadC)") (class "Default")
      (node (ref "D1") (pin "C") (pinfunction "C_C") (pintype "passive"))
      (node (ref "R10") (pin "2") (pinfunction "2_2") (pintype "passive"))
    )
    (net (code "20") (name "Net-(D2-PadA)") (class "Default")
      (node (ref "D2") (pin "A") (pinfunction "A_A") (pintype "passive"))
      (node (ref "R6") (pin "2") (pinfunction "2_2") (pintype "passive"))
    )
    (net (code "21") (name "Net-(D5-PadC)") (class "Default")
      (node (ref "D5") (pin "C") (pinfunction "C_C") (pintype "passive"))
      (node (ref "R11") (pin "2") (pinfunction "2_2") (pintype "passive"))
    )
    (net (code "22") (name "Net-(J3-CC1)") (class "Default")
      (node (ref "J3") (pin "A5") (pinfunction "CC1_A5") (pintype "bidirectional"))
      (node (ref "R1") (pin "1") (pinfunction "1_1") (pintype "passive"))
    )
    (net (code "23") (name "Net-(J3-CC2)") (class "Default")
      (node (ref "J3") (pin "B5") (pinfunction "CC2_B5") (pintype "bidirectional"))
      (node (ref "R5") (pin "1") (pinfunction "1_1") (pintype "passive"))
    )
    (net (code "24") (name "Net-(Q2-B)") (class "Default")
      (node (ref "Q2") (pin "1") (pinfunction "B_1") (pintype "passive"))
      (node (ref "R12") (pin "2") (pinfunction "2_2") (pintype "passive"))
    )
    (net (code "25") (name "Net-(Q2-C)") (class "Default")
      (node (ref "D8") (pin "A") (pinfunction "A_A") (pintype "passive"))
      (node (ref "LS1") (pin "1") (pinfunction "1_1") (pintype "passive"))
      (node (ref "Q2") (pin "3") (pinfunction "C_3") (pintype "passive"))
    )
    (net (code "26") (name "Net-(SW1-2)") (class "Default")
      (node (ref "D3") (pin "C") (pinfunction "C_C") (pintype "passive"))
      (node (ref "D4") (pin "C") (pinfunction "C_C") (pintype "passive"))
      (node (ref "SW1") (pin "8") (pinfunction "2_8") (pintype "passive"))
    )
    (net (code "27") (name "Net-(U1-PB6(XTAL1{slash}TOSC1))") (class "Default")
      (node (ref "Q1") (pin "1") (pinfunction "1_1") (pintype "passive"))
      (node (ref "U1") (pin "7") (pinfunction "PB6(XTAL1/TOSC1)_7") (pintype "bidirectional"))
    )
    (net (code "28") (name "Net-(U1-PB7(XTAL2{slash}TOSC2))") (class "Default")
      (node (ref "Q1") (pin "3") (pinfunction "3_3") (pintype "passive"))
      (node (ref "U1") (pin "8") (pinfunction "PB7(XTAL2/TOSC2)_8") (pintype "bidirectional"))
    )
    (net (code "29") (name "Net-(U3-DO)") (class "Default")
      (node (ref "U3") (pin "1") (pinfunction "DO_1") (pintype "output"))
      (node (ref "U4") (pin "3") (pinfunction "DI_3") (pintype "input"))
    )
    (net (code "30") (name "Net-(U4-DO)") (class "Default")
      (node (ref "U4") (pin "1") (pinfunction "DO_1") (pintype "output"))
      (node (ref "U9") (pin "3") (pinfunction "DI_3") (pintype "input"))
    )
    (net (code "31") (name "Net-(U10-DI)") (class "Default")
      (node (ref "U10") (pin "3") (pinfunction "DI_3") (pintype "input"))
      (node (ref "U9") (pin "1") (pinfunction "DO_1") (pintype "output"))
    )
    (net (code "32") (name "Net-(U10-DO)") (class "Default")
      (node (ref "U10") (pin "1") (pinfunction "DO_1") (pintype "output"))
      (node (ref "U11") (pin "3") (pinfunction "DI_3") (pintype "input"))
    )
    (net (code "33") (name "Net-(U11-DO)") (class "Default")
      (node (ref "U11") (pin "1") (pinfunction "DO_1") (pintype "output"))
      (node (ref "U12") (pin "3") (pinfunction "DI_3") (pintype "input"))
    )
    (net (code "34") (name "Net-(U12-DO)") (class "Default")
      (node (ref "U12") (pin "1") (pinfunction "DO_1") (pintype "output"))
      (node (ref "U13") (pin "3") (pinfunction "DI_3") (pintype "input"))
    )
    (net (code "35") (name "Net-(U13-DO)") (class "Default")
      (node (ref "U13") (pin "1") (pinfunction "DO_1") (pintype "output"))
      (node (ref "U14") (pin "3") (pinfunction "DI_3") (pintype "input"))
    )
    (net (code "36") (name "Net-(U14-DO)") (class "Default")
      (node (ref "U14") (pin "1") (pinfunction "DO_1") (pintype "output"))
      (node (ref "U15") (pin "3") (pinfunction "DI_3") (pintype "input"))
    )
    (net (code "37") (name "Net-(U15-DO)") (class "Default")
      (node (ref "U15") (pin "1") (pinfunction "DO_1") (pintype "output"))
      (node (ref "U16") (pin "3") (pinfunction "DI_3") (pintype "input"))
    )
    (net (code "38") (name "Net-(U16-DO)") (class "Default")
      (node (ref "U16") (pin "1") (pinfunction "DO_1") (pintype "output"))
      (node (ref "U17") (pin "3") (pinfunction "DI_3") (pintype "input"))
    )
    (net (code "39") (name "Net-(U17-DO)") (class "Default")
      (node (ref "U17") (pin "1") (pinfunction "DO_1") (pintype "output"))
      (node (ref "U18") (pin "3") (pinfunction "DI_3") (pintype "input"))
    )
    (net (code "40") (name "Net-(U18-DO)") (class "Default")
      (node (ref "U18") (pin "1") (pinfunction "DO_1") (pintype "output"))
      (node (ref "U19") (pin "3") (pinfunction "DI_3") (pintype "input"))
    )
    (net (code "41") (name "Net-(U19-DO)") (class "Default")
      (node (ref "U19") (pin "1") (pinfunction "DO_1") (pintype "output"))
      (node (ref "U20") (pin "3") (pinfunction "DI_3") (pintype "input"))
    )
    (net (code "42") (name "Net-(U20-DO)") (class "Default")
      (node (ref "U20") (pin "1") (pinfunction "DO_1") (pintype "output"))
      (node (ref "U21") (pin "3") (pinfunction "DI_3") (pintype "input"))
    )
    (net (code "43") (name "Net-(U21-DO)") (class "Default")
      (node (ref "U21") (pin "1") (pinfunction "DO_1") (pintype "output"))
      (node (ref "U22") (pin "3") (pinfunction "DI_3") (pintype "input"))
    )
    (net (code "44") (name "PE0") (class "Default")
      (node (ref "TP2") (pin "TP") (pinfunction "TP_TP") (pintype "input"))
      (node (ref "U1") (pin "3") (pinfunction "GND_3") (pintype "bidirectional"))
    )
    (net (code "45") (name "PE1") (class "Default")
      (node (ref "TP1") (pin "TP") (pinfunction "TP_TP") (pintype "input"))
      (node (ref "U1") (pin "6") (pinfunction "VCC_6") (pintype "bidirectional"))
    )
    (net (code "46") (name "RESET") (class "Default")
      (node (ref "C2") (pin "1") (pinfunction "1_1") (pintype "passive"))
      (node (ref "J1") (pin "1") (pinfunction "1_1") (pintype "passive"))
      (node (ref "R2") (pin "1") (pinfunction "1_1") (pintype "passive"))
      (node (ref "S1") (pin "4") (pinfunction "4_4") (pintype "passive"))
      (node (ref "U1") (pin "29") (pinfunction "PC6(/RESET)_29") (pintype "bidirectional"))
    )
    (net (code "47") (name "RIGHT_IN") (class "Default")
      (node (ref "SV1") (pin "2") (pinfunction "2_2") (pintype "passive"))
      (node (ref "U1") (pin "9") (pinfunction "PD5(T1)_9") (pintype "bidirectional"))
    )
    (net (code "48") (name "RIGHT_OUT") (class "Default")
      (node (ref "SV1") (pin "1") (pinfunction "1_1") (pintype "passive"))
      (node (ref "U1") (pin "10") (pinfunction "PD6(AIN0)_10") (pintype "bidirectional"))
    )
    (net (code "49") (name "RXI") (class "Default")
      (node (ref "JP3") (pin "1") (pinfunction "1_1") (pintype "passive"))
      (node (ref "U1") (pin "30") (pinfunction "PD0(RXD)_30") (pintype "bidirectional"))
    )
    (net (code "50") (name "SAO_IO1") (class "Default")
      (node (ref "J1") (pin "4") (pinfunction "4_4") (pintype "passive"))
      (node (ref "J2") (pin "5") (pinfunction "5_5") (pintype "passive"))
      (node (ref "U1") (pin "15") (pinfunction "PB3(MOSI/OC2)_15") (pintype "bidirectional"))
    )
    (net (code "51") (name "SAO_IO2") (class "Default")
      (node (ref "J1") (pin "5") (pinfunction "5_5") (pintype "passive"))
      (node (ref "J2") (pin "6") (pinfunction "6_6") (pintype "passive"))
      (node (ref "U1") (pin "16") (pinfunction "PB4(MISO)_16") (pintype "bidirectional"))
    )
    (net (code "52") (name "SCL") (class "Default")
      (node (ref "J2") (pin "4") (pinfunction "4_4") (pintype "passive"))
      (node (ref "U1") (pin "28") (pinfunction "PC5(ADC5/SCL)_28") (pintype "bidirectional"))
    )
    (net (code "53") (name "SDA") (class "Default")
      (node (ref "J2") (pin "3") (pinfunction "3_3") (pintype "passive"))
      (node (ref "U1") (pin "27") (pinfunction "PC4(ADC4/SDA)_27") (pintype "bidirectional"))
    )
    (net (code "54") (name "SENSE_LEFT") (class "Default")
      (node (ref "R3") (pin "2") (pinfunction "2_2") (pintype "passive"))
      (node (ref "SV2") (pin "1") (pinfunction "1_1") (pintype "passive"))
      (node (ref "U1") (pin "2") (pinfunction "PD4(XCK/T0)_2") (pintype "bidirectional"))
    )
    (net (code "55") (name "SENSE_RIGHT") (class "Default")
      (node (ref "R4") (pin "1") (pinfunction "1_1") (pintype "passive"))
      (node (ref "SV1") (pin "3") (pinfunction "3_3") (pintype "passive"))
      (node (ref "U1") (pin "11") (pinfunction "PD7(AIN1)_11") (pintype "bidirectional"))
    )
    (net (code "56") (name "SPK") (class "Default")
      (node (ref "R12") (pin "1") (pinfunction "1_1") (pintype "passive"))
      (node (ref "U1") (pin "12") (pinfunction "PB0(ICP)_12") (pintype "bidirectional"))
    )
    (net (code "57") (name "TXO") (class "Default")
      (node (ref "JP2") (pin "1") (pinfunction "1_1") (pintype "passive"))
      (node (ref "U1") (pin "31") (pinfunction "PD1(TXD)_31") (pintype "bidirectional"))
    )
    (net (code "58") (name "USB_DN") (class "Default")
      (node (ref "J3") (pin "A7") (pinfunction "DN1_A7") (pintype "bidirectional"))
      (node (ref "J3") (pin "B7") (pinfunction "DN2_B7") (pintype "bidirectional"))
      (node (ref "U7") (pin "6") (pinfunction "UD-_6") (pintype "bidirectional"))
      (node (ref "U8") (pin "6") (pinfunction "C5_6") (pintype "passive"))
    )
    (net (code "59") (name "USB_DP") (class "Default")
      (node (ref "J3") (pin "A6") (pinfunction "DP1_A6") (pintype "bidirectional"))
      (node (ref "J3") (pin "B6") (pinfunction "DP2_B6") (pintype "bidirectional"))
      (node (ref "U7") (pin "5") (pinfunction "UD+_5") (pintype "bidirectional"))
      (node (ref "U8") (pin "5") (pinfunction "C4_5") (pintype "passive"))
    )
    (net (code "60") (name "VBAT") (class "Default")
      (node (ref "D4") (pin "A") (pinfunction "A_A") (pintype "passive"))
      (node (ref "U6") (pin "1") (pinfunction "1_1") (pintype "passive"))
    )
    (net (code "61") (name "VBUS") (class "Default")
      (node (ref "D3") (pin "A") (pinfunction "A_A") (pintype "passive"))
      (node (ref "J3") (pin "A4/B9") (pinfunction "VBUS_A4/B9") (pintype "power_in"))
      (node (ref "J3") (pin "B4/A9") (pinfunction "VBUS_B4/A9") (pintype "power_in"))
      (node (ref "U8") (pin "4") (pinfunction "C3_4") (pintype "passive"))
    )
    (net (code "62") (name "VDD") (class "Default")
      (node (ref "C10") (pin "2") (pinfunction "2_2") (pintype "passive"))
      (node (ref "C11") (pin "2") (pinfunction "2_2") (pintype "passive"))
      (node (ref "C12") (pin "2") (pinfunction "2_2") (pintype "passive"))
      (node (ref "C13") (pin "2") (pinfunction "2_2") (pintype "passive"))
      (node (ref "C14") (pin "2") (pinfunction "2_2") (pintype "passive"))
      (node (ref "C15") (pin "2") (pinfunction "2_2") (pintype "passive"))
      (node (ref "C16") (pin "2") (pinfunction "2_2") (pintype "passive"))
      (node (ref "C17") (pin "2") (pinfunction "2_2") (pintype "passive"))
      (node (ref "C18") (pin "2") (pinfunction "2_2") (pintype "passive"))
      (node (ref "C19") (pin "2") (pinfunction "2_2") (pintype "passive"))
      (node (ref "C21") (pin "1") (pinfunction "1_1") (pintype "passive"))
      (node (ref "C4") (pin "2") (pinfunction "2_2") (pintype "passive"))
      (node (ref "C5") (pin "2") (pinfunction "2_2") (pintype "passive"))
      (node (ref "C6") (pin "2") (pinfunction "2_2") (pintype "passive"))
      (node (ref "C7") (pin "2") (pinfunction "2_2") (pintype "passive"))
      (node (ref "C8") (pin "2") (pinfunction "2_2") (pintype "passive"))
      (node (ref "C9") (pin "2") (pinfunction "2_2") (pintype "passive"))
      (node (ref "D5") (pin "A") (pinfunction "A_A") (pintype "passive"))
      (node (ref "R7") (pin "2") (pinfunction "2_2") (pintype "passive"))
      (node (ref "SW1") (pin "7") (pinfunction "1_7") (pintype "passive"))
      (node (ref "U10") (pin "4") (pinfunction "VDD_4") (pintype "power_in"))
      (node (ref "U11") (pin "4") (pinfunction "VDD_4") (pintype "power_in"))
      (node (ref "U12") (pin "4") (pinfunction "VDD_4") (pintype "power_in"))
      (node (ref "U13") (pin "4") (pinfunction "VDD_4") (pintype "power_in"))
      (node (ref "U14") (pin "4") (pinfunction "VDD_4") (pintype "power_in"))
      (node (ref "U15") (pin "4") (pinfunction "VDD_4") (pintype "power_in"))
      (node (ref "U16") (pin "4") (pinfunction "VDD_4") (pintype "power_in"))
      (node (ref "U17") (pin "4") (pinfunction "VDD_4") (pintype "power_in"))
      (node (ref "U18") (pin "4") (pinfunction "VDD_4") (pintype "power_in"))
      (node (ref "U19") (pin "4") (pinfunction "VDD_4") (pintype "power_in"))
      (node (ref "U2") (pin "1") (pinfunction "IN_1") (pintype "power_in"))
      (node (ref "U20") (pin "4") (pinfunction "VDD_4") (pintype "power_in"))
      (node (ref "U21") (pin "4") (pinfunction "VDD_4") (pintype "power_in"))
      (node (ref "U22") (pin "4") (pinfunction "VDD_4") (pintype "power_in"))
      (node (ref "U3") (pin "4") (pinfunction "VDD_4") (pintype "power_in"))
      (node (ref "U4") (pin "4") (pinfunction "VDD_4") (pintype "power_in"))
      (node (ref "U9") (pin "4") (pinfunction "VDD_4") (pintype "power_in"))
    )
    (net (code "63") (name "unconnected-(J3-SBU1-PadA8)") (class "Default")
      (node (ref "J3") (pin "A8") (pinfunction "SBU1_A8") (pintype "bidirectional"))
    )
    (net (code "64") (name "unconnected-(J3-SBU2-PadB8)") (class "Default")
      (node (ref "J3") (pin "B8") (pinfunction "SBU2_B8") (pintype "bidirectional"))
    )
    (net (code "65") (name "unconnected-(S1-Pad1)") (class "Default")
      (node (ref "S1") (pin "1") (pinfunction "1_1") (pintype "passive"))
    )
    (net (code "66") (name "unconnected-(S1-Pad3)") (class "Default")
      (node (ref "S1") (pin "3") (pinfunction "3_3") (pintype "passive"))
    )
    (net (code "67") (name "unconnected-(S2-Pad1)") (class "Default")
      (node (ref "S2") (pin "1") (pinfunction "1_1") (pintype "passive"))
    )
    (net (code "68") (name "unconnected-(S2-Pad3)") (class "Default")
      (node (ref "S2") (pin "3") (pinfunction "3_3") (pintype "passive"))
    )
    (net (code "69") (name "unconnected-(S3-Pad1)") (class "Default")
      (node (ref "S3") (pin "1") (pinfunction "1_1") (pintype "passive"))
    )
    (net (code "70") (name "unconnected-(S3-Pad3)") (class "Default")
      (node (ref "S3") (pin "3") (pinfunction "3_3") (pintype "passive"))
    )
    (net (code "71") (name "unconnected-(S4-Pad1)") (class "Default")
      (node (ref "S4") (pin "1") (pinfunction "1_1") (pintype "passive"))
    )
    (net (code "72") (name "unconnected-(S4-Pad3)") (class "Default")
      (node (ref "S4") (pin "3") (pinfunction "3_3") (pintype "passive"))
    )
    (net (code "73") (name "unconnected-(S5-Pad1)") (class "Default")
      (node (ref "S5") (pin "1") (pinfunction "1_1") (pintype "passive"))
    )
    (net (code "74") (name "unconnected-(S5-Pad3)") (class "Default")
      (node (ref "S5") (pin "3") (pinfunction "3_3") (pintype "passive"))
    )
    (net (code "75") (name "unconnected-(S6-Pad1)") (class "Default")
      (node (ref "S6") (pin "1") (pinfunction "1_1") (pintype "passive"))
    )
    (net (code "76") (name "unconnected-(S6-Pad3)") (class "Default")
      (node (ref "S6") (pin "3") (pinfunction "3_3") (pintype "passive"))
    )
    (net (code "77") (name "unconnected-(S7-Pad1)") (class "Default")
      (node (ref "S7") (pin "1") (pinfunction "1_1") (pintype "passive"))
    )
    (net (code "78") (name "unconnected-(S7-Pad3)") (class "Default")
      (node (ref "S7") (pin "3") (pinfunction "3_3") (pintype "passive"))
    )
    (net (code "79") (name "unconnected-(SW1-3-Pad9)") (class "Default")
      (node (ref "SW1") (pin "9") (pinfunction "3_9") (pintype "passive"))
    )
    (net (code "80") (name "unconnected-(U1-PB2(SS{slash}OC1B)-Pad14)") (class "Default")
      (node (ref "U1") (pin "14") (pinfunction "PB2(SS/OC1B)_14") (pintype "bidirectional"))
    )
    (net (code "81") (name "unconnected-(U2-P4-Pad4)") (class "Default")
      (node (ref "U2") (pin "4") (pinfunction "P4_4") (pintype "bidirectional"))
    )
    (net (code "82") (name "unconnected-(U7-NC.-Pad7)") (class "Default")
      (node (ref "U7") (pin "7") (pinfunction "NC._7") (pintype "no_connect"))
    )
    (net (code "83") (name "unconnected-(U7-R232-Pad15)") (class "Default")
      (node (ref "U7") (pin "15") (pinfunction "R232_15") (pintype "input"))
    )
    (net (code "84") (name "unconnected-(U7-~{CTS}-Pad9)") (class "Default")
      (node (ref "U7") (pin "9") (pinfunction "~{CTS}_9") (pintype "input"))
    )
    (net (code "85") (name "unconnected-(U7-~{DCD}-Pad12)") (class "Default")
      (node (ref "U7") (pin "12") (pinfunction "~{DCD}_12") (pintype "input"))
    )
    (net (code "86") (name "unconnected-(U7-~{DSR}-Pad10)") (class "Default")
      (node (ref "U7") (pin "10") (pinfunction "~{DSR}_10") (pintype "input"))
    )
    (net (code "87") (name "unconnected-(U7-~{OUT}-Pad8)") (class "Default")
      (node (ref "U7") (pin "8") (pinfunction "~{OUT}_8") (pintype "output"))
    )
    (net (code "88") (name "unconnected-(U7-~{RI}-Pad11)") (class "Default")
      (node (ref "U7") (pin "11") (pinfunction "~{RI}_11") (pintype "input"))
    )
    (net (code "89") (name "unconnected-(U7-~{RTS}-Pad14)") (class "Default")
      (node (ref "U7") (pin "14") (pinfunction "~{RTS}_14") (pintype "output"))
    )
    (net (code "90") (name "unconnected-(U8-C1-Pad1)") (class "Default")
      (node (ref "U8") (pin "1") (pinfunction "C1_1") (pintype "passive"))
    )
    (net (code "91") (name "unconnected-(U8-C2-Pad3)") (class "Default")
      (node (ref "U8") (pin "3") (pinfunction "C2_3") (pintype "passive"))
    )
    (net (code "92") (name "unconnected-(U22-DO-Pad1)") (class "Default")
      (node (ref "U22") (pin "1") (pinfunction "DO_1") (pintype "output"))
    )
  )
)
